# LoRa.net
KiCad netlist of a schematic drawn in Altium Designer
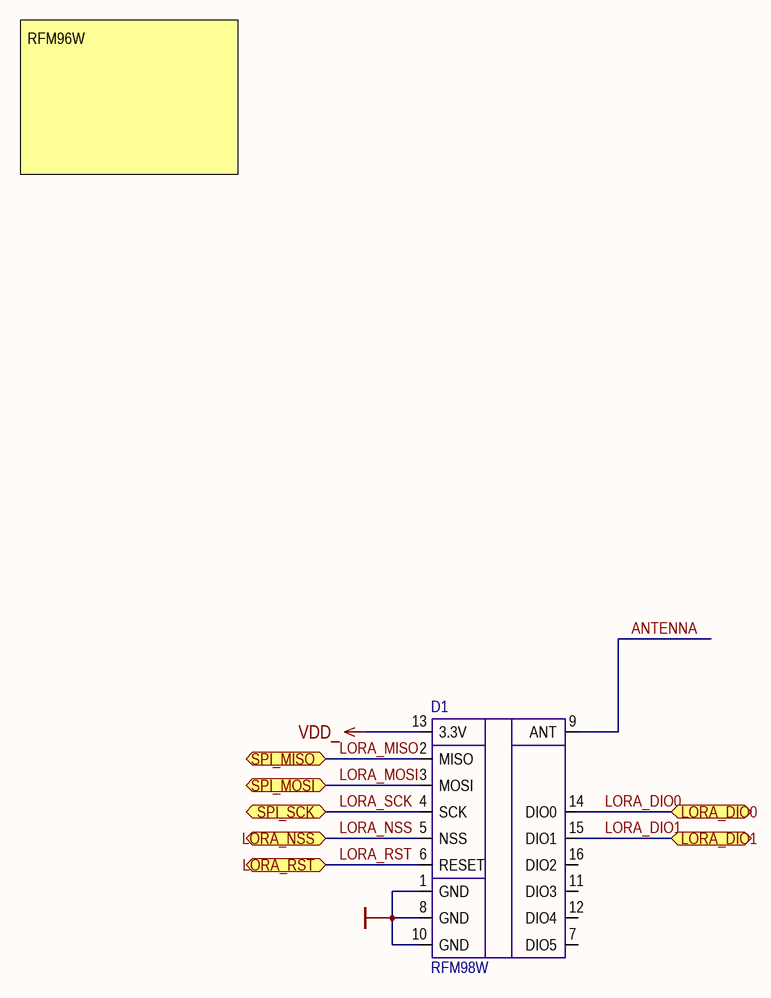
[diagram p0: LoRa.SchDoc]

(export (version "E")
  (design (tool "Eeschema 10.0.6"))
  (components
    (comp (ref "D1")
      (value "RFM98W")
      (footprint "RFM98W")
      (description "LoRa modem")
      (libsource (lib "11.Other") (part "RFM98W"))
    )
  )
  (nets
    (net (code "1") (name "/ANTENNA") (class "Default")
      (node (ref "D1") (pin "9") (pinfunction "ANT_9") (pintype "passive"))
    )
    (net (code "2") (name "/LORA_DIO0") (class "Default")
      (node (ref "D1") (pin "14") (pinfunction "DIO0_14") (pintype "passive"))
    )
    (net (code "3") (name "/LORA_DIO1") (class "Default")
      (node (ref "D1") (pin "15") (pinfunction "DIO1_15") (pintype "passive"))
    )
    (net (code "4") (name "/LORA_MISO") (class "Default")
      (node (ref "D1") (pin "2") (pinfunction "MISO_2") (pintype "passive"))
    )
    (net (code "5") (name "/LORA_MOSI") (class "Default")
      (node (ref "D1") (pin "3") (pinfunction "MOSI_3") (pintype "passive"))
    )
    (net (code "6") (name "/LORA_NSS") (class "Default")
      (node (ref "D1") (pin "5") (pinfunction "NSS_5") (pintype "passive"))
    )
    (net (code "7") (name "/LORA_RST") (class "Default")
      (node (ref "D1") (pin "6") (pinfunction "RESET_6") (pintype "passive"))
    )
    (net (code "8") (name "/LORA_SCK") (class "Default")
      (node (ref "D1") (pin "4") (pinfunction "SCK_4") (pintype "passive"))
    )
    (net (code "9") (name "GND") (class "Default")
      (node (ref "D1") (pin "1") (pinfunction "GND_1") (pintype "passive"))
      (node (ref "D1") (pin "10") (pinfunction "GND_10") (pintype "passive"))
      (node (ref "D1") (pin "8") (pinfunction "GND_8") (pintype "passive"))
    )
    (net (code "10") (name "VDD_") (class "Default")
      (node (ref "D1") (pin "13") (pinfunction "3.3V_13") (pintype "passive"))
    )
    (net (code "11") (name "unconnected-(D1-DIO2-Pad16)") (class "Default")
      (node (ref "D1") (pin "16") (pinfunction "DIO2_16") (pintype "passive"))
    )
    (net (code "12") (name "unconnected-(D1-DIO3-Pad11)") (class "Default")
      (node (ref "D1") (pin "11") (pinfunction "DIO3_11") (pintype "passive"))
    )
    (net (code "13") (name "unconnected-(D1-DIO4-Pad12)") (class "Default")
      (node (ref "D1") (pin "12") (pinfunction "DIO4_12") (pintype "passive"))
    )
    (net (code "14") (name "unconnected-(D1-DIO5-Pad7)") (class "Default")
      (node (ref "D1") (pin "7") (pinfunction "DIO5_7") (pintype "passive"))
    )
  )
)
